# mePed.net
KiCad netlist of a schematic drawn in EAGLE
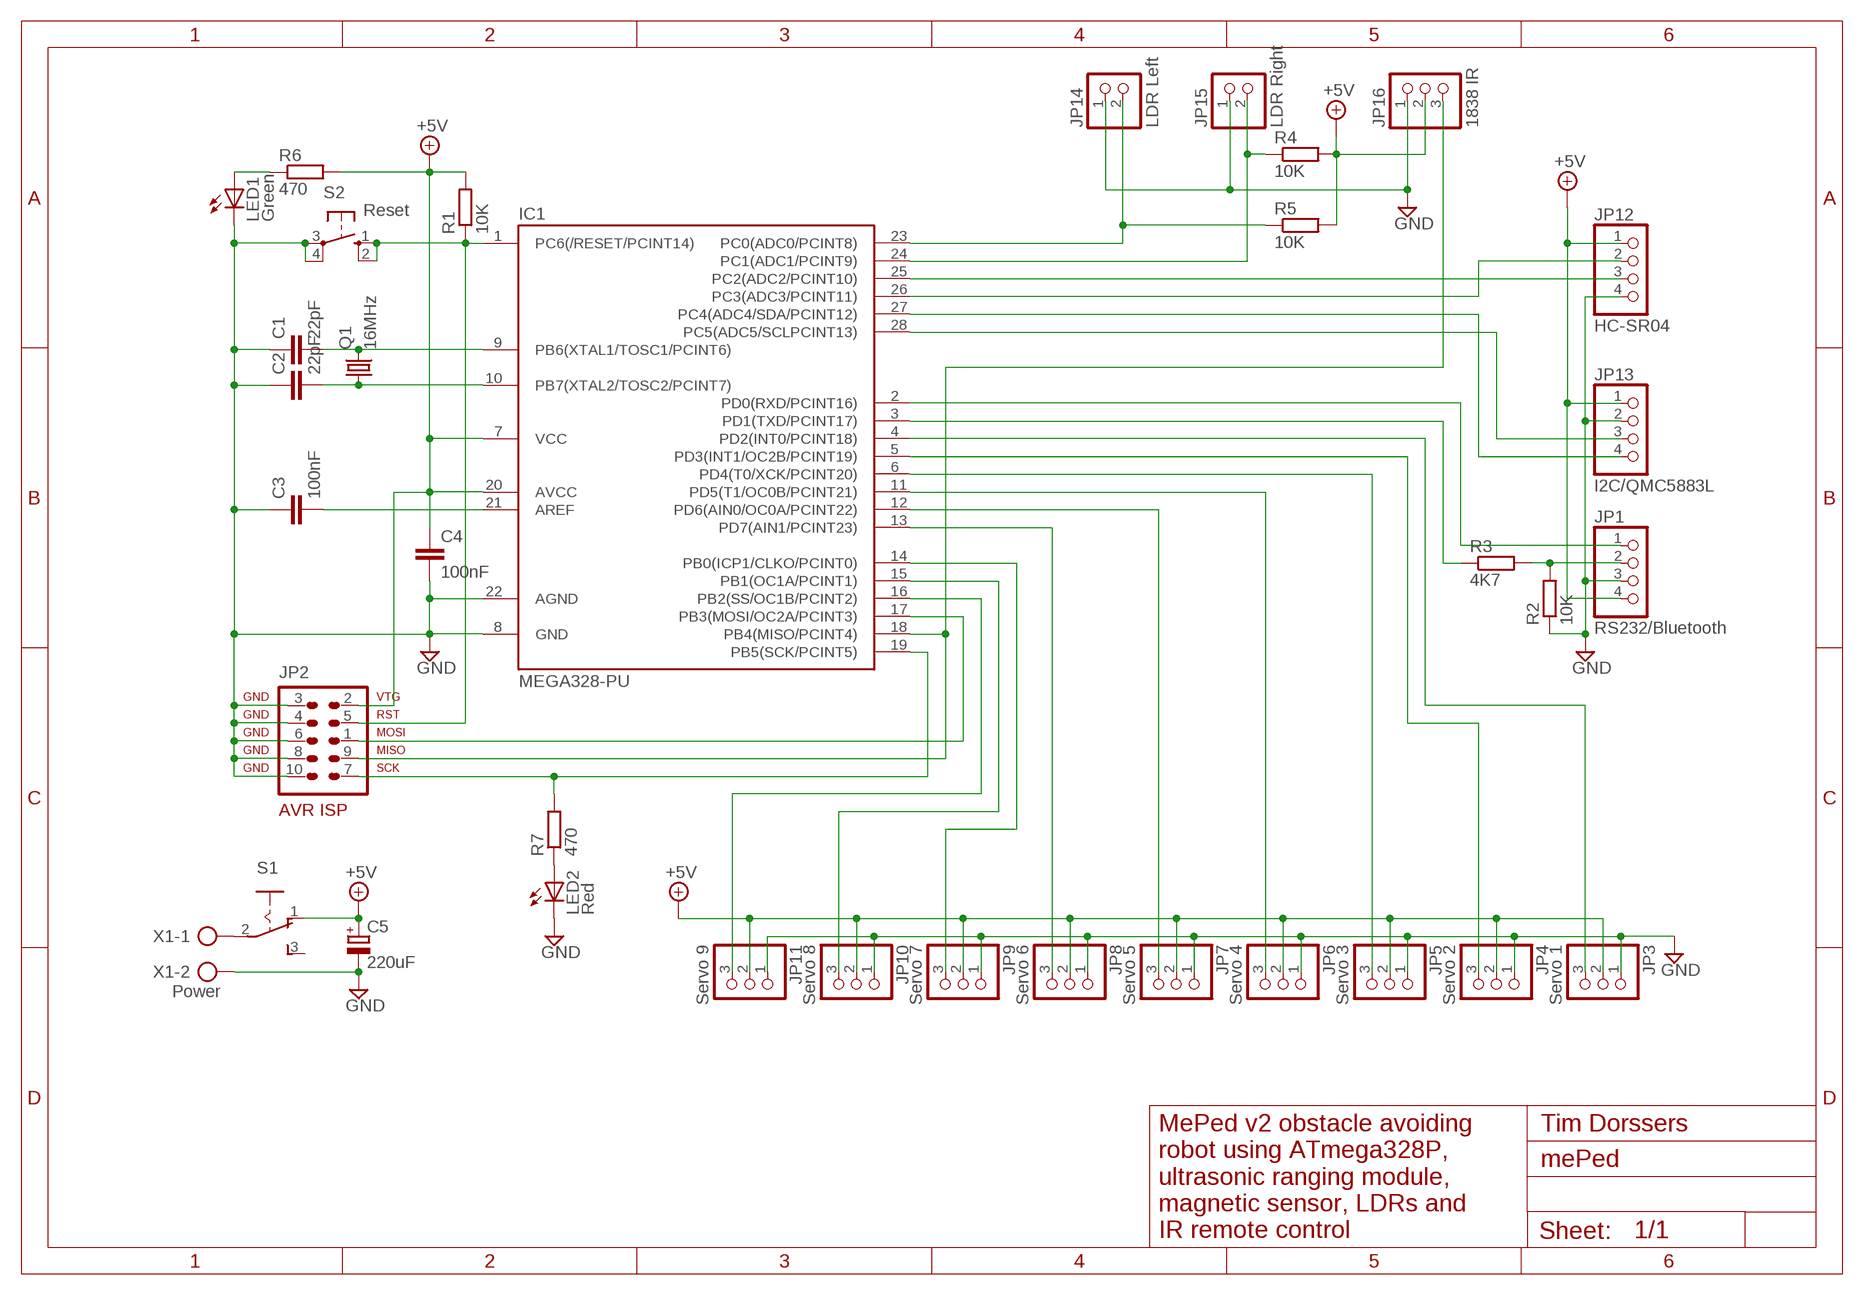
[diagram p0: schematic, sheet 1]

(export (version "E")
  (design (tool "Eeschema 10.0.6"))
  (components
    (comp (ref "C1")
      (value "22pF")
      (footprint "eagle-import:C025-024X044")
      (libsource (lib "eagle-import") (part "C-EU025-024X044"))
    )
    (comp (ref "C2")
      (value "22pF")
      (footprint "eagle-import:C025-024X044")
      (libsource (lib "eagle-import") (part "C-EU025-024X044"))
    )
    (comp (ref "C3")
      (value "100nF")
      (footprint "eagle-import:C025-025X050")
      (libsource (lib "eagle-import") (part "C-EU025-025X050"))
    )
    (comp (ref "C4")
      (value "100nF")
      (footprint "eagle-import:C025-025X050")
      (libsource (lib "eagle-import") (part "C-EU025-025X050"))
    )
    (comp (ref "C5")
      (value "220uF")
      (footprint "eagle-import:B45181A")
      (libsource (lib "eagle-import") (part "CPOL-EUB45181A"))
    )
    (comp (ref "IC1")
      (value "MEGA328-PU")
      (footprint "eagle-import:DIL28-3")
      (libsource (lib "eagle-import") (part "MEGA48/88/168-PU"))
    )
    (comp (ref "JP1")
      (value "RS232/Bluetooth")
      (footprint "eagle-import:1X04")
      (libsource (lib "eagle-import") (part "PINHD-1X4"))
    )
    (comp (ref "JP2")
      (value "AVR-ISP-10")
      (footprint "eagle-import:AVR-ISP-10")
      (libsource (lib "eagle-import") (part "AVR-ISP-10"))
    )
    (comp (ref "JP3")
      (value "Servo 1")
      (footprint "eagle-import:1X03")
      (libsource (lib "eagle-import") (part "PINHD-1X3"))
    )
    (comp (ref "JP4")
      (value "Servo 2")
      (footprint "eagle-import:1X03")
      (libsource (lib "eagle-import") (part "PINHD-1X3"))
    )
    (comp (ref "JP5")
      (value "Servo 3")
      (footprint "eagle-import:1X03")
      (libsource (lib "eagle-import") (part "PINHD-1X3"))
    )
    (comp (ref "JP6")
      (value "Servo 4")
      (footprint "eagle-import:1X03")
      (libsource (lib "eagle-import") (part "PINHD-1X3"))
    )
    (comp (ref "JP7")
      (value "Servo 5")
      (footprint "eagle-import:1X03")
      (libsource (lib "eagle-import") (part "PINHD-1X3"))
    )
    (comp (ref "JP8")
      (value "Servo 6")
      (footprint "eagle-import:1X03")
      (libsource (lib "eagle-import") (part "PINHD-1X3"))
    )
    (comp (ref "JP9")
      (value "Servo 7")
      (footprint "eagle-import:1X03")
      (libsource (lib "eagle-import") (part "PINHD-1X3"))
    )
    (comp (ref "JP10")
      (value "Servo 8")
      (footprint "eagle-import:1X03")
      (libsource (lib "eagle-import") (part "PINHD-1X3"))
    )
    (comp (ref "JP11")
      (value "Servo 9")
      (footprint "eagle-import:1X03")
      (libsource (lib "eagle-import") (part "PINHD-1X3"))
    )
    (comp (ref "JP12")
      (value "HC-SR04")
      (footprint "eagle-import:1X04")
      (libsource (lib "eagle-import") (part "PINHD-1X4"))
    )
    (comp (ref "JP13")
      (value "I2C/QMC5883L")
      (footprint "eagle-import:1X04")
      (libsource (lib "eagle-import") (part "PINHD-1X4"))
    )
    (comp (ref "JP14")
      (value "LDR Left")
      (footprint "eagle-import:1X02")
      (libsource (lib "eagle-import") (part "PINHD-1X2"))
    )
    (comp (ref "JP15")
      (value "LDR Right")
      (footprint "eagle-import:1X02")
      (libsource (lib "eagle-import") (part "PINHD-1X2"))
    )
    (comp (ref "JP16")
      (value "1838 IR")
      (footprint "eagle-import:1X03")
      (libsource (lib "eagle-import") (part "PINHD-1X3"))
    )
    (comp (ref "LED1")
      (value "Green")
      (footprint "eagle-import:LED5MM")
      (libsource (lib "eagle-import") (part "LED5MM"))
    )
    (comp (ref "LED2")
      (value "Red")
      (footprint "eagle-import:LED5MM")
      (libsource (lib "eagle-import") (part "LED5MM"))
    )
    (comp (ref "Q1")
      (value "16MHz")
      (footprint "eagle-import:HC49_S")
      (libsource (lib "eagle-import") (part "CRYSTALHC49S"))
    )
    (comp (ref "R1")
      (value "10K")
      (footprint "eagle-import:0204_7")
      (libsource (lib "eagle-import") (part "R-EU_0204/7"))
    )
    (comp (ref "R2")
      (value "10K")
      (footprint "eagle-import:0204_7")
      (libsource (lib "eagle-import") (part "R-EU_0204/7"))
    )
    (comp (ref "R3")
      (value "4K7")
      (footprint "eagle-import:0204_7")
      (libsource (lib "eagle-import") (part "R-EU_0204/7"))
    )
    (comp (ref "R4")
      (value "10K")
      (footprint "eagle-import:0204_7")
      (libsource (lib "eagle-import") (part "resistor_R-EU_0204/7"))
    )
    (comp (ref "R5")
      (value "10K")
      (footprint "eagle-import:0204_7")
      (libsource (lib "eagle-import") (part "resistor_R-EU_0204/7"))
    )
    (comp (ref "R6")
      (value "470")
      (footprint "eagle-import:0204_7")
      (libsource (lib "eagle-import") (part "resistor_R-EU_0204/7"))
    )
    (comp (ref "R7")
      (value "470")
      (footprint "eagle-import:0204_7")
      (libsource (lib "eagle-import") (part "resistor_R-EU_0204/7"))
    )
    (comp (ref "S1")
      (value "255SB")
      (footprint "eagle-import:255SB")
      (libsource (lib "eagle-import") (part "255SB"))
    )
    (comp (ref "S2")
      (value "Reset")
      (footprint "eagle-import:B3F-10XX")
      (fields (field (name "MPN") "B3F-1000"))
      (libsource (lib "eagle-import") (part "10-XX"))
    )
    (comp (ref "X1")
      (value "Power")
      (footprint "eagle-import:AK300_2")
      (libsource (lib "eagle-import") (part "AK300/2"))
    )
  )
  (nets
    (net (code "1") (name "+5V") (class "Default")
      (node (ref "C4") (pin "1") (pinfunction "1_1") (pintype "passive"))
      (node (ref "C5") (pin "+") (pinfunction "+_+") (pintype "passive"))
      (node (ref "IC1") (pin "20") (pinfunction "AVCC_20") (pintype "passive"))
      (node (ref "IC1") (pin "7") (pinfunction "VCC_7") (pintype "power_in"))
      (node (ref "JP1") (pin "4") (pinfunction "4_4") (pintype "passive"))
      (node (ref "JP10") (pin "2") (pinfunction "2_2") (pintype "passive"))
      (node (ref "JP11") (pin "2") (pinfunction "2_2") (pintype "passive"))
      (node (ref "JP12") (pin "1") (pinfunction "1_1") (pintype "passive"))
      (node (ref "JP13") (pin "1") (pinfunction "1_1") (pintype "passive"))
      (node (ref "JP16") (pin "2") (pinfunction "2_2") (pintype "passive"))
      (node (ref "JP2") (pin "2") (pinfunction "2_2") (pintype "passive"))
      (node (ref "JP3") (pin "2") (pinfunction "2_2") (pintype "passive"))
      (node (ref "JP4") (pin "2") (pinfunction "2_2") (pintype "passive"))
      (node (ref "JP5") (pin "2") (pinfunction "2_2") (pintype "passive"))
      (node (ref "JP6") (pin "2") (pinfunction "2_2") (pintype "passive"))
      (node (ref "JP7") (pin "2") (pinfunction "2_2") (pintype "passive"))
      (node (ref "JP8") (pin "2") (pinfunction "2_2") (pintype "passive"))
      (node (ref "JP9") (pin "2") (pinfunction "2_2") (pintype "passive"))
      (node (ref "R1") (pin "2") (pinfunction "2_2") (pintype "passive"))
      (node (ref "R4") (pin "2") (pinfunction "2_2") (pintype "passive"))
      (node (ref "R5") (pin "2") (pinfunction "2_2") (pintype "passive"))
      (node (ref "R6") (pin "2") (pinfunction "2_2") (pintype "passive"))
      (node (ref "S1") (pin "1") (pinfunction "O_1") (pintype "passive"))
    )
    (net (code "2") (name "GND") (class "Default")
      (node (ref "C1") (pin "1") (pinfunction "1_1") (pintype "passive"))
      (node (ref "C2") (pin "1") (pinfunction "1_1") (pintype "passive"))
      (node (ref "C3") (pin "1") (pinfunction "1_1") (pintype "passive"))
      (node (ref "C4") (pin "2") (pinfunction "2_2") (pintype "passive"))
      (node (ref "C5") (pin "-") (pinfunction "-_-") (pintype "passive"))
      (node (ref "IC1") (pin "22") (pinfunction "AGND_22") (pintype "power_in"))
      (node (ref "IC1") (pin "8") (pinfunction "GND_8") (pintype "power_in"))
      (node (ref "JP1") (pin "3") (pinfunction "3_3") (pintype "passive"))
      (node (ref "JP10") (pin "1") (pinfunction "1_1") (pintype "passive"))
      (node (ref "JP11") (pin "1") (pinfunction "1_1") (pintype "passive"))
      (node (ref "JP12") (pin "4") (pinfunction "4_4") (pintype "passive"))
      (node (ref "JP13") (pin "2") (pinfunction "2_2") (pintype "passive"))
      (node (ref "JP14") (pin "1") (pinfunction "1_1") (pintype "passive"))
      (node (ref "JP15") (pin "1") (pinfunction "1_1") (pintype "passive"))
      (node (ref "JP16") (pin "1") (pinfunction "1_1") (pintype "passive"))
      (node (ref "JP2") (pin "10") (pinfunction "10_10") (pintype "passive"))
      (node (ref "JP2") (pin "3") (pinfunction "3_3") (pintype "passive"))
      (node (ref "JP2") (pin "4") (pinfunction "4_4") (pintype "passive"))
      (node (ref "JP2") (pin "6") (pinfunction "6_6") (pintype "passive"))
      (node (ref "JP2") (pin "8") (pinfunction "8_8") (pintype "passive"))
      (node (ref "JP3") (pin "1") (pinfunction "1_1") (pintype "passive"))
      (node (ref "JP4") (pin "1") (pinfunction "1_1") (pintype "passive"))
      (node (ref "JP5") (pin "1") (pinfunction "1_1") (pintype "passive"))
      (node (ref "JP6") (pin "1") (pinfunction "1_1") (pintype "passive"))
      (node (ref "JP7") (pin "1") (pinfunction "1_1") (pintype "passive"))
      (node (ref "JP8") (pin "1") (pinfunction "1_1") (pintype "passive"))
      (node (ref "JP9") (pin "1") (pinfunction "1_1") (pintype "passive"))
      (node (ref "LED1") (pin "K") (pinfunction "C_K") (pintype "passive"))
      (node (ref "LED2") (pin "K") (pinfunction "C_K") (pintype "passive"))
      (node (ref "R2") (pin "1") (pinfunction "1_1") (pintype "passive"))
      (node (ref "S2") (pin "3") (pinfunction "P_3") (pintype "passive"))
      (node (ref "S2") (pin "4") (pinfunction "P1_4") (pintype "passive"))
      (node (ref "X1") (pin "2") (pinfunction "KL_2") (pintype "passive"))
    )
    (net (code "3") (name "Net-(IC1-AREF)") (class "Default")
      (node (ref "C3") (pin "2") (pinfunction "2_2") (pintype "passive"))
      (node (ref "IC1") (pin "21") (pinfunction "AREF_21") (pintype "passive"))
    )
    (net (code "4") (name "Net-(IC1-PB0(ICP1{slash}CLKO{slash}PCINT0))") (class "Default")
      (node (ref "IC1") (pin "14") (pinfunction "PB0(ICP1/CLKO/PCINT0)_14") (pintype "bidirectional"))
      (node (ref "JP9") (pin "3") (pinfunction "3_3") (pintype "passive"))
    )
    (net (code "5") (name "Net-(IC1-PB1(OC1A{slash}PCINT1))") (class "Default")
      (node (ref "IC1") (pin "15") (pinfunction "PB1(OC1A/PCINT1)_15") (pintype "bidirectional"))
      (node (ref "JP10") (pin "3") (pinfunction "3_3") (pintype "passive"))
    )
    (net (code "6") (name "Net-(IC1-PB2(SS{slash}OC1B{slash}PCINT2))") (class "Default")
      (node (ref "IC1") (pin "16") (pinfunction "PB2(SS/OC1B/PCINT2)_16") (pintype "bidirectional"))
      (node (ref "JP11") (pin "3") (pinfunction "3_3") (pintype "passive"))
    )
    (net (code "7") (name "Net-(IC1-PB3(MOSI{slash}OC2A{slash}PCINT3))") (class "Default")
      (node (ref "IC1") (pin "17") (pinfunction "PB3(MOSI/OC2A/PCINT3)_17") (pintype "bidirectional"))
      (node (ref "JP2") (pin "1") (pinfunction "1_1") (pintype "passive"))
    )
    (net (code "8") (name "Net-(IC1-PB4(MISO{slash}PCINT4))") (class "Default")
      (node (ref "IC1") (pin "18") (pinfunction "PB4(MISO/PCINT4)_18") (pintype "bidirectional"))
      (node (ref "JP16") (pin "3") (pinfunction "3_3") (pintype "passive"))
      (node (ref "JP2") (pin "9") (pinfunction "9_9") (pintype "passive"))
    )
    (net (code "9") (name "Net-(IC1-PB5(SCK{slash}PCINT5))") (class "Default")
      (node (ref "IC1") (pin "19") (pinfunction "PB5(SCK/PCINT5)_19") (pintype "bidirectional"))
      (node (ref "JP2") (pin "7") (pinfunction "7_7") (pintype "passive"))
      (node (ref "R7") (pin "2") (pinfunction "2_2") (pintype "passive"))
    )
    (net (code "10") (name "Net-(IC1-PB6(XTAL1{slash}TOSC1{slash}PCINT6))") (class "Default")
      (node (ref "C1") (pin "2") (pinfunction "2_2") (pintype "passive"))
      (node (ref "IC1") (pin "9") (pinfunction "PB6(XTAL1/TOSC1/PCINT6)_9") (pintype "bidirectional"))
      (node (ref "Q1") (pin "2") (pinfunction "2_2") (pintype "passive"))
    )
    (net (code "11") (name "Net-(IC1-PB7(XTAL2{slash}TOSC2{slash}PCINT7))") (class "Default")
      (node (ref "C2") (pin "2") (pinfunction "2_2") (pintype "passive"))
      (node (ref "IC1") (pin "10") (pinfunction "PB7(XTAL2/TOSC2/PCINT7)_10") (pintype "bidirectional"))
      (node (ref "Q1") (pin "1") (pinfunction "1_1") (pintype "passive"))
    )
    (net (code "12") (name "Net-(IC1-PC0(ADC0{slash}PCINT8))") (class "Default")
      (node (ref "IC1") (pin "23") (pinfunction "PC0(ADC0/PCINT8)_23") (pintype "bidirectional"))
      (node (ref "JP14") (pin "2") (pinfunction "2_2") (pintype "passive"))
      (node (ref "R5") (pin "1") (pinfunction "1_1") (pintype "passive"))
    )
    (net (code "13") (name "Net-(IC1-PC1(ADC1{slash}PCINT9))") (class "Default")
      (node (ref "IC1") (pin "24") (pinfunction "PC1(ADC1/PCINT9)_24") (pintype "bidirectional"))
      (node (ref "JP15") (pin "2") (pinfunction "2_2") (pintype "passive"))
      (node (ref "R4") (pin "1") (pinfunction "1_1") (pintype "passive"))
    )
    (net (code "14") (name "Net-(IC1-PC2(ADC2{slash}PCINT10))") (class "Default")
      (node (ref "IC1") (pin "25") (pinfunction "PC2(ADC2/PCINT10)_25") (pintype "bidirectional"))
      (node (ref "JP12") (pin "3") (pinfunction "3_3") (pintype "passive"))
    )
    (net (code "15") (name "Net-(IC1-PC3(ADC3{slash}PCINT11))") (class "Default")
      (node (ref "IC1") (pin "26") (pinfunction "PC3(ADC3/PCINT11)_26") (pintype "bidirectional"))
      (node (ref "JP12") (pin "2") (pinfunction "2_2") (pintype "passive"))
    )
    (net (code "16") (name "Net-(IC1-PC4(ADC4{slash}SDA{slash}PCINT12))") (class "Default")
      (node (ref "IC1") (pin "27") (pinfunction "PC4(ADC4/SDA/PCINT12)_27") (pintype "bidirectional"))
      (node (ref "JP13") (pin "4") (pinfunction "4_4") (pintype "passive"))
    )
    (net (code "17") (name "Net-(IC1-PC5(ADC5{slash}SCLPCINT13))") (class "Default")
      (node (ref "IC1") (pin "28") (pinfunction "PC5(ADC5/SCLPCINT13)_28") (pintype "bidirectional"))
      (node (ref "JP13") (pin "3") (pinfunction "3_3") (pintype "passive"))
    )
    (net (code "18") (name "Net-(IC1-PC6({slash}RESET{slash}PCINT14))") (class "Default")
      (node (ref "IC1") (pin "1") (pinfunction "PC6(/RESET/PCINT14)_1") (pintype "bidirectional"))
      (node (ref "JP2") (pin "5") (pinfunction "5_5") (pintype "passive"))
      (node (ref "R1") (pin "1") (pinfunction "1_1") (pintype "passive"))
      (node (ref "S2") (pin "1") (pinfunction "S_1") (pintype "passive"))
      (node (ref "S2") (pin "2") (pinfunction "S1_2") (pintype "passive"))
    )
    (net (code "19") (name "Net-(IC1-PD0(RXD{slash}PCINT16))") (class "Default")
      (node (ref "IC1") (pin "2") (pinfunction "PD0(RXD/PCINT16)_2") (pintype "bidirectional"))
      (node (ref "JP1") (pin "1") (pinfunction "1_1") (pintype "passive"))
    )
    (net (code "20") (name "Net-(IC1-PD1(TXD{slash}PCINT17))") (class "Default")
      (node (ref "IC1") (pin "3") (pinfunction "PD1(TXD/PCINT17)_3") (pintype "bidirectional"))
      (node (ref "R3") (pin "1") (pinfunction "1_1") (pintype "passive"))
    )
    (net (code "21") (name "Net-(IC1-PD2(INT0{slash}PCINT18))") (class "Default")
      (node (ref "IC1") (pin "4") (pinfunction "PD2(INT0/PCINT18)_4") (pintype "bidirectional"))
      (node (ref "JP3") (pin "3") (pinfunction "3_3") (pintype "passive"))
    )
    (net (code "22") (name "Net-(IC1-PD3(INT1{slash}OC2B{slash}PCINT19))") (class "Default")
      (node (ref "IC1") (pin "5") (pinfunction "PD3(INT1/OC2B/PCINT19)_5") (pintype "bidirectional"))
      (node (ref "JP4") (pin "3") (pinfunction "3_3") (pintype "passive"))
    )
    (net (code "23") (name "Net-(IC1-PD4(T0{slash}XCK{slash}PCINT20))") (class "Default")
      (node (ref "IC1") (pin "6") (pinfunction "PD4(T0/XCK/PCINT20)_6") (pintype "bidirectional"))
      (node (ref "JP5") (pin "3") (pinfunction "3_3") (pintype "passive"))
    )
    (net (code "24") (name "Net-(IC1-PD5(T1{slash}OC0B{slash}PCINT21))") (class "Default")
      (node (ref "IC1") (pin "11") (pinfunction "PD5(T1/OC0B/PCINT21)_11") (pintype "bidirectional"))
      (node (ref "JP6") (pin "3") (pinfunction "3_3") (pintype "passive"))
    )
    (net (code "25") (name "Net-(IC1-PD6(AIN0{slash}OC0A{slash}PCINT22))") (class "Default")
      (node (ref "IC1") (pin "12") (pinfunction "PD6(AIN0/OC0A/PCINT22)_12") (pintype "bidirectional"))
      (node (ref "JP7") (pin "3") (pinfunction "3_3") (pintype "passive"))
    )
    (net (code "26") (name "Net-(IC1-PD7(AIN1{slash}PCINT23))") (class "Default")
      (node (ref "IC1") (pin "13") (pinfunction "PD7(AIN1/PCINT23)_13") (pintype "bidirectional"))
      (node (ref "JP8") (pin "3") (pinfunction "3_3") (pintype "passive"))
    )
    (net (code "27") (name "Net-(JP1-Pad2)") (class "Default")
      (node (ref "JP1") (pin "2") (pinfunction "2_2") (pintype "passive"))
      (node (ref "R2") (pin "2") (pinfunction "2_2") (pintype "passive"))
      (node (ref "R3") (pin "2") (pinfunction "2_2") (pintype "passive"))
    )
    (net (code "28") (name "Net-(LED1-PadA)") (class "Default")
      (node (ref "LED1") (pin "A") (pinfunction "A_A") (pintype "passive"))
      (node (ref "R6") (pin "1") (pinfunction "1_1") (pintype "passive"))
    )
    (net (code "29") (name "Net-(LED2-PadA)") (class "Default")
      (node (ref "LED2") (pin "A") (pinfunction "A_A") (pintype "passive"))
      (node (ref "R7") (pin "1") (pinfunction "1_1") (pintype "passive"))
    )
    (net (code "30") (name "Net-(S1-P)") (class "Default")
      (node (ref "S1") (pin "2") (pinfunction "P_2") (pintype "passive"))
      (node (ref "X1") (pin "1") (pinfunction "KL_1") (pintype "passive"))
    )
    (net (code "31") (name "unconnected-(S1-S-Pad3)") (class "Default")
      (node (ref "S1") (pin "3") (pinfunction "S_3") (pintype "passive"))
    )
  )
)
